# GPS_logger_Shield-v10.net
KiCad netlist of a schematic drawn in EAGLE
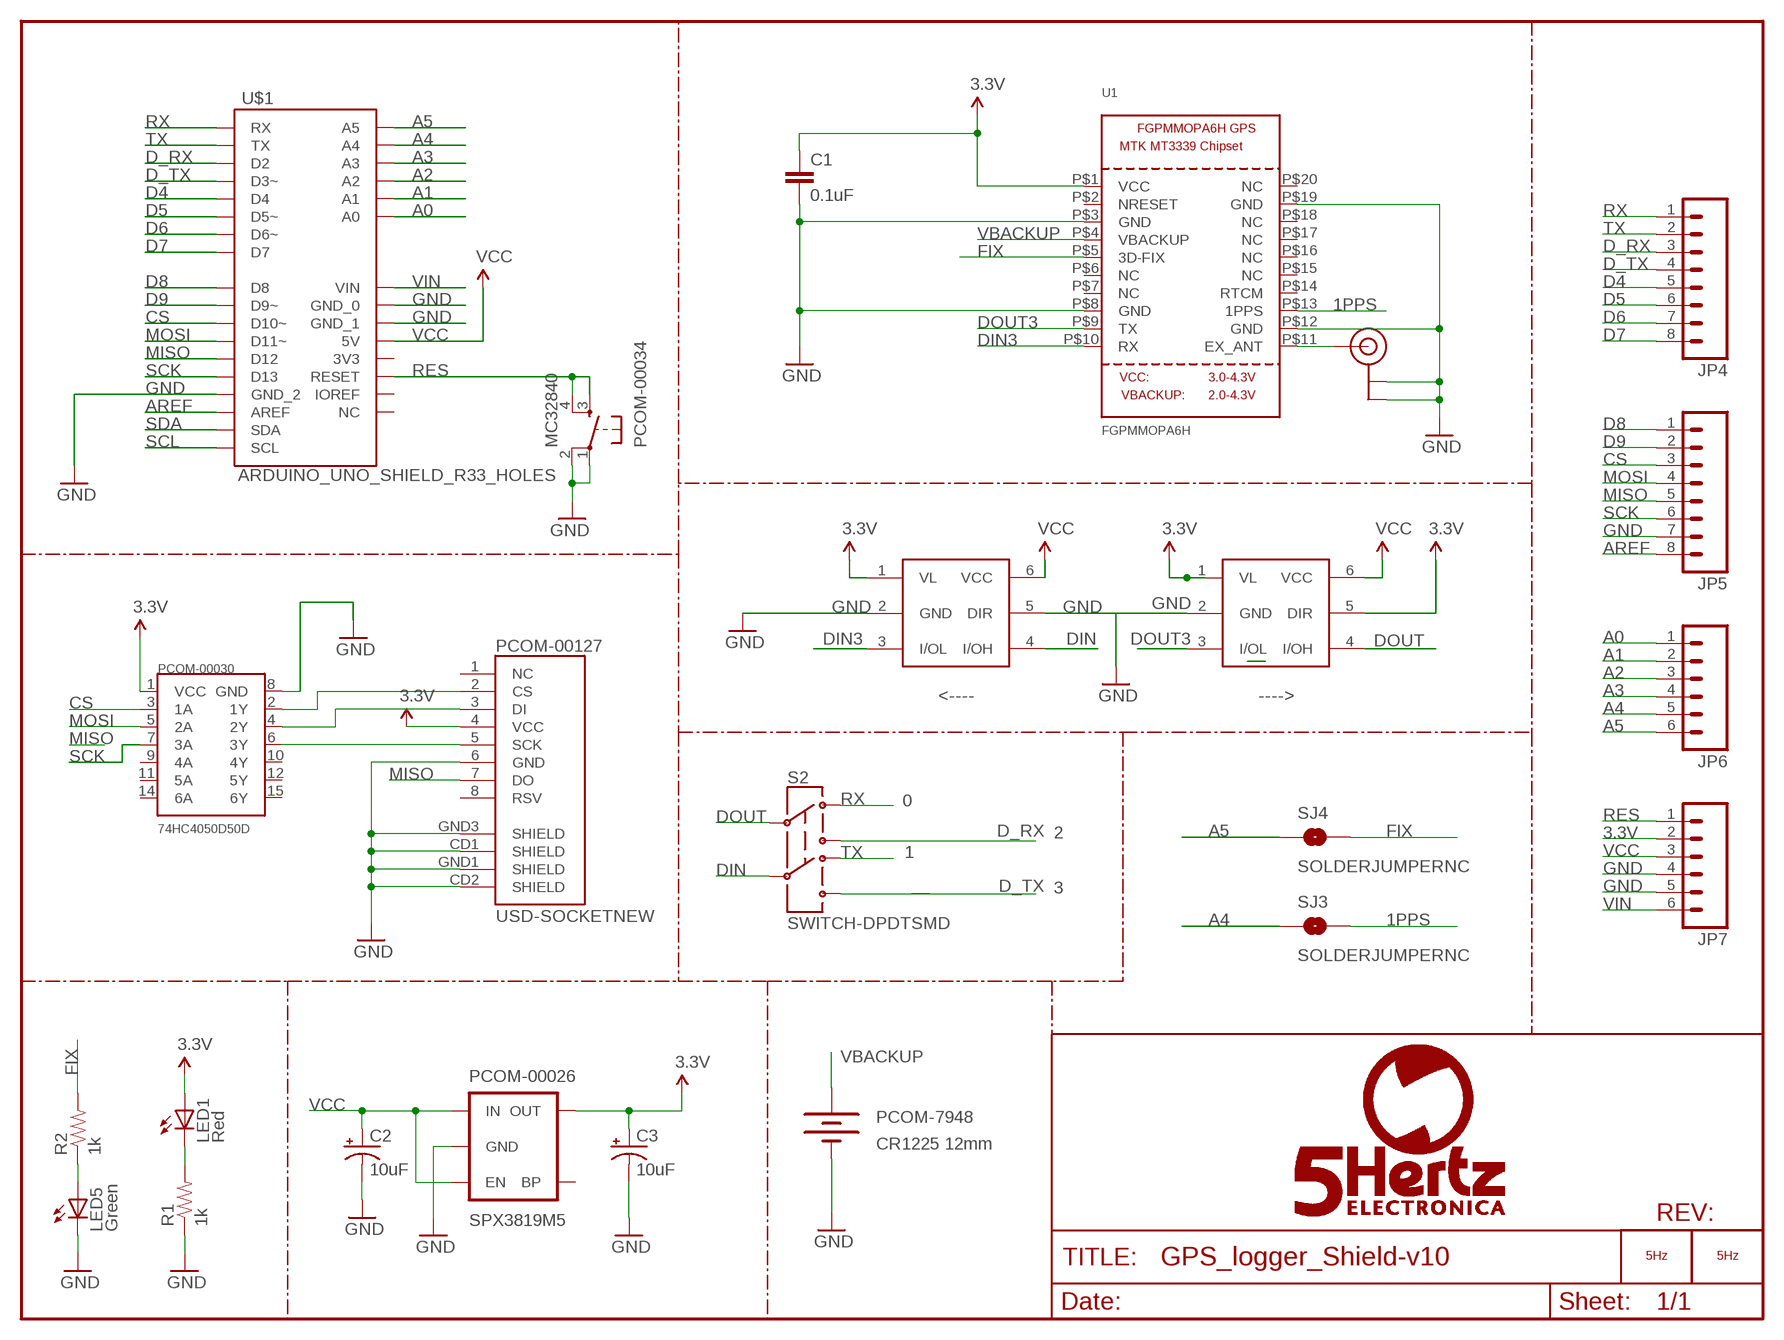
[diagram p0: schematic, sheet 1]

(export (version "E")
  (design (tool "Eeschema 10.0.6"))
  (components
    (comp (ref "C1")
      (value "0.1uF")
      (footprint "eagle-import:0603-CAP")
      (libsource (lib "eagle-import") (part "CAP0603-CAP"))
    )
    (comp (ref "C2")
      (value "10uF")
      (footprint "eagle-import:EIA3216")
      (libsource (lib "eagle-import") (part "CAP_POL1206"))
    )
    (comp (ref "C3")
      (value "10uF")
      (footprint "eagle-import:EIA3216")
      (libsource (lib "eagle-import") (part "CAP_POL1206"))
    )
    (comp (ref "JP4")
      (value "M08")
      (footprint "eagle-import:1X08")
      (libsource (lib "eagle-import") (part "M08"))
    )
    (comp (ref "JP5")
      (value "M08")
      (footprint "eagle-import:1X08")
      (libsource (lib "eagle-import") (part "M08"))
    )
    (comp (ref "JP6")
      (value "M06SIP")
      (footprint "eagle-import:1X06")
      (libsource (lib "eagle-import") (part "M06SIP"))
    )
    (comp (ref "JP7")
      (value "M06SIP")
      (footprint "eagle-import:1X06")
      (libsource (lib "eagle-import") (part "M06SIP"))
    )
    (comp (ref "LED1")
      (value "Red")
      (footprint "eagle-import:LED-0603")
      (libsource (lib "eagle-import") (part "LED0603"))
    )
    (comp (ref "LED5")
      (value "Green")
      (footprint "eagle-import:LED-0603")
      (libsource (lib "eagle-import") (part "LED0603"))
    )
    (comp (ref "LOGO1")
      (value "LOGO_5HZ_H_COOPER_15MM")
      (footprint "eagle-import:5HZ_LOGO_H_COOPER_15MM")
      (libsource (lib "eagle-import") (part "LOGO_5HZ_H_COOPER_15MM"))
    )
    (comp (ref "LOGO2")
      (value "LOGO_5HZ_MAIN_10MM")
      (footprint "eagle-import:5HZ_LOGO_MAIN_10MM")
      (libsource (lib "eagle-import") (part "LOGO_5HZ_MAIN_10MM"))
    )
    (comp (ref "PCOM-00026")
      (value "SPX3819M5")
      (footprint "eagle-import:SOT23-5")
      (libsource (lib "eagle-import") (part "V_REG_LDOSMD"))
    )
    (comp (ref "PCOM-00030")
      (value "74HC4050D50D")
      (footprint "eagle-import:SO016")
      (libsource (lib "eagle-import") (part "HEX_CONVERTER"))
    )
    (comp (ref "PCOM-00034")
      (value "MC32840")
      (footprint "eagle-import:TACTILE_SWITCH_SMD")
      (libsource (lib "eagle-import") (part "TAC_SWITCHSMD"))
    )
    (comp (ref "PCOM-00127")
      (value "USD-SOCKETNEW")
      (footprint "eagle-import:MICRO-SD-SOCKET-PP")
      (libsource (lib "eagle-import") (part "USD-SOCKETNEW"))
    )
    (comp (ref "PCOM-7948")
      (value "CR1225 12mm")
      (footprint "eagle-import:BATTCON_12MM_PTH")
      (libsource (lib "eagle-import") (part "BATTERY12PTH"))
    )
    (comp (ref "R1")
      (value "1k")
      (footprint "eagle-import:0603-RES")
      (libsource (lib "eagle-import") (part "RESISTOR0603-RES"))
    )
    (comp (ref "R2")
      (value "1k")
      (footprint "eagle-import:0603-RES")
      (libsource (lib "eagle-import") (part "RESISTOR0603-RES"))
    )
    (comp (ref "S2")
      (value "SWITCH-DPDTSMD")
      (footprint "eagle-import:AYZ0202")
      (libsource (lib "eagle-import") (part "SWITCH-DPDTSMD"))
    )
    (comp (ref "SJ3")
      (value "SOLDERJUMPERNC")
      (footprint "eagle-import:SJ_2S")
      (libsource (lib "eagle-import") (part "SOLDERJUMPERNC"))
    )
    (comp (ref "SJ4")
      (value "SOLDERJUMPERNC")
      (footprint "eagle-import:SJ_2S")
      (libsource (lib "eagle-import") (part "SOLDERJUMPERNC"))
    )
    (comp (ref "U$1")
      (value "ARDUINO_UNO_SHIELD_R33_HOLES")
      (footprint "eagle-import:UNO_R3_SHIELD_3_HOLES_NO_SILK")
      (libsource (lib "eagle-import") (part "ARDUINO_UNO_SHIELD_R33_HOLES"))
    )
    (comp (ref "U$7")
      (value "MAX337")
      (footprint "eagle-import:SOT-363")
      (libsource (lib "eagle-import") (part "MAX337"))
    )
    (comp (ref "U$8")
      (value "MAX337")
      (footprint "eagle-import:SOT-363")
      (libsource (lib "eagle-import") (part "MAX337"))
    )
    (comp (ref "U$20")
      (value "U.FL")
      (footprint "eagle-import:U.FL")
      (libsource (lib "eagle-import") (part "U.FL"))
    )
    (comp (ref "U1")
      (value "FGPMMOPA6H")
      (footprint "eagle-import:FGPMMOPA6H")
      (libsource (lib "eagle-import") (part "GPS_FGPMMOPA6H"))
    )
  )
  (nets
    (net (code "1") (name "/1PPS") (class "Default")
      (node (ref "SJ3") (pin "2") (pinfunction "2_2") (pintype "passive"))
      (node (ref "U1") (pin "P$13") (pinfunction "1PPS_P$13") (pintype "bidirectional"))
    )
    (net (code "2") (name "/A0") (class "Default")
      (node (ref "JP6") (pin "1") (pinfunction "1_1") (pintype "passive"))
      (node (ref "U$1") (pin "A0") (pinfunction "A0_A0") (pintype "bidirectional"))
    )
    (net (code "3") (name "/A1") (class "Default")
      (node (ref "JP6") (pin "2") (pinfunction "2_2") (pintype "passive"))
      (node (ref "U$1") (pin "A1") (pinfunction "A1_A1") (pintype "bidirectional"))
    )
    (net (code "4") (name "/A2") (class "Default")
      (node (ref "JP6") (pin "3") (pinfunction "3_3") (pintype "passive"))
      (node (ref "U$1") (pin "A2") (pinfunction "A2_A2") (pintype "bidirectional"))
    )
    (net (code "5") (name "/A3") (class "Default")
      (node (ref "JP6") (pin "4") (pinfunction "4_4") (pintype "passive"))
      (node (ref "U$1") (pin "A3") (pinfunction "A3_A3") (pintype "bidirectional"))
    )
    (net (code "6") (name "/A4") (class "Default")
      (node (ref "JP6") (pin "5") (pinfunction "5_5") (pintype "passive"))
      (node (ref "SJ3") (pin "1") (pinfunction "1_1") (pintype "passive"))
      (node (ref "U$1") (pin "A4") (pinfunction "A4_A4") (pintype "bidirectional"))
    )
    (net (code "7") (name "/A5") (class "Default")
      (node (ref "JP6") (pin "6") (pinfunction "6_6") (pintype "passive"))
      (node (ref "SJ4") (pin "1") (pinfunction "1_1") (pintype "passive"))
      (node (ref "U$1") (pin "A5") (pinfunction "A5_A5") (pintype "bidirectional"))
    )
    (net (code "8") (name "/AREF") (class "Default")
      (node (ref "JP5") (pin "8") (pinfunction "8_8") (pintype "passive"))
      (node (ref "U$1") (pin "AREF") (pinfunction "AREF_AREF") (pintype "bidirectional"))
    )
    (net (code "9") (name "/CS") (class "Default")
      (node (ref "JP5") (pin "3") (pinfunction "3_3") (pintype "passive"))
      (node (ref "PCOM-00030") (pin "3") (pinfunction "1A_3") (pintype "bidirectional"))
      (node (ref "U$1") (pin "D10") (pinfunction "D10~{}_D10") (pintype "bidirectional"))
    )
    (net (code "10") (name "/D4") (class "Default")
      (node (ref "JP4") (pin "5") (pinfunction "5_5") (pintype "passive"))
      (node (ref "U$1") (pin "D4") (pinfunction "D4_D4") (pintype "bidirectional"))
    )
    (net (code "11") (name "/D5") (class "Default")
      (node (ref "JP4") (pin "6") (pinfunction "6_6") (pintype "passive"))
      (node (ref "U$1") (pin "D5") (pinfunction "D5~{}_D5") (pintype "bidirectional"))
    )
    (net (code "12") (name "/D6") (class "Default")
      (node (ref "JP4") (pin "7") (pinfunction "7_7") (pintype "passive"))
      (node (ref "U$1") (pin "D6") (pinfunction "D6~{}_D6") (pintype "bidirectional"))
    )
    (net (code "13") (name "/D7") (class "Default")
      (node (ref "JP4") (pin "8") (pinfunction "8_8") (pintype "passive"))
      (node (ref "U$1") (pin "D7") (pinfunction "D7_D7") (pintype "bidirectional"))
    )
    (net (code "14") (name "/D8") (class "Default")
      (node (ref "JP5") (pin "1") (pinfunction "1_1") (pintype "passive"))
      (node (ref "U$1") (pin "D8") (pinfunction "D8_D8") (pintype "bidirectional"))
    )
    (net (code "15") (name "/D9") (class "Default")
      (node (ref "JP5") (pin "2") (pinfunction "2_2") (pintype "passive"))
      (node (ref "U$1") (pin "D9") (pinfunction "D9~{}_D9") (pintype "bidirectional"))
    )
    (net (code "16") (name "/DIN") (class "Default")
      (node (ref "S2") (pin "5") (pinfunction "5_5") (pintype "bidirectional"))
      (node (ref "U$7") (pin "4") (pinfunction "I/OH_4") (pintype "bidirectional"))
    )
    (net (code "17") (name "/DIN3") (class "Default")
      (node (ref "U$7") (pin "3") (pinfunction "I/OL_3") (pintype "bidirectional"))
      (node (ref "U1") (pin "P$10") (pinfunction "RX_P$10") (pintype "bidirectional"))
    )
    (net (code "18") (name "/DOUT") (class "Default")
      (node (ref "S2") (pin "2") (pinfunction "2_2") (pintype "bidirectional"))
      (node (ref "U$8") (pin "4") (pinfunction "I/OH_4") (pintype "bidirectional"))
    )
    (net (code "19") (name "/DOUT3") (class "Default")
      (node (ref "U$8") (pin "3") (pinfunction "I/OL_3") (pintype "bidirectional"))
      (node (ref "U1") (pin "P$9") (pinfunction "TX_P$9") (pintype "bidirectional"))
    )
    (net (code "20") (name "/D_RX") (class "Default")
      (node (ref "JP4") (pin "3") (pinfunction "3_3") (pintype "passive"))
      (node (ref "S2") (pin "3") (pinfunction "3_3") (pintype "bidirectional"))
      (node (ref "U$1") (pin "D2") (pinfunction "D2_D2") (pintype "bidirectional"))
    )
    (net (code "21") (name "/D_TX") (class "Default")
      (node (ref "JP4") (pin "4") (pinfunction "4_4") (pintype "passive"))
      (node (ref "S2") (pin "6") (pinfunction "6_6") (pintype "bidirectional"))
      (node (ref "U$1") (pin "D3") (pinfunction "D3~{}_D3") (pintype "bidirectional"))
    )
    (net (code "22") (name "/FIX") (class "Default")
      (node (ref "R2") (pin "2") (pinfunction "2_2") (pintype "passive"))
      (node (ref "SJ4") (pin "2") (pinfunction "2_2") (pintype "passive"))
      (node (ref "U1") (pin "P$5") (pinfunction "3D-FIX_P$5") (pintype "bidirectional"))
    )
    (net (code "23") (name "/MISO") (class "Default")
      (node (ref "JP5") (pin "5") (pinfunction "5_5") (pintype "passive"))
      (node (ref "PCOM-00127") (pin "7") (pinfunction "DO_7") (pintype "bidirectional"))
      (node (ref "U$1") (pin "D12") (pinfunction "D12_D12") (pintype "bidirectional"))
    )
    (net (code "24") (name "/MOSI") (class "Default")
      (node (ref "JP5") (pin "4") (pinfunction "4_4") (pintype "passive"))
      (node (ref "PCOM-00030") (pin "5") (pinfunction "2A_5") (pintype "bidirectional"))
      (node (ref "U$1") (pin "D11") (pinfunction "D11~{}_D11") (pintype "bidirectional"))
    )
    (net (code "25") (name "/RES") (class "Default")
      (node (ref "JP7") (pin "1") (pinfunction "1_1") (pintype "passive"))
      (node (ref "PCOM-00034") (pin "3") (pinfunction "3_3") (pintype "passive"))
      (node (ref "PCOM-00034") (pin "4") (pinfunction "4_4") (pintype "passive"))
      (node (ref "U$1") (pin "RES") (pinfunction "RESET_RES") (pintype "bidirectional"))
    )
    (net (code "26") (name "/RX") (class "Default")
      (node (ref "JP4") (pin "1") (pinfunction "1_1") (pintype "passive"))
      (node (ref "S2") (pin "1") (pinfunction "1_1") (pintype "bidirectional"))
      (node (ref "U$1") (pin "RX") (pinfunction "RX_RX") (pintype "bidirectional"))
    )
    (net (code "27") (name "/SCK") (class "Default")
      (node (ref "JP5") (pin "6") (pinfunction "6_6") (pintype "passive"))
      (node (ref "PCOM-00030") (pin "7") (pinfunction "3A_7") (pintype "bidirectional"))
      (node (ref "U$1") (pin "D13") (pinfunction "D13_D13") (pintype "bidirectional"))
    )
    (net (code "28") (name "/SCL") (class "Default")
      (node (ref "U$1") (pin "SCL") (pinfunction "SCL_SCL") (pintype "bidirectional"))
    )
    (net (code "29") (name "/SDA") (class "Default")
      (node (ref "U$1") (pin "SDA") (pinfunction "SDA_SDA") (pintype "bidirectional"))
    )
    (net (code "30") (name "/TX") (class "Default")
      (node (ref "JP4") (pin "2") (pinfunction "2_2") (pintype "passive"))
      (node (ref "S2") (pin "4") (pinfunction "4_4") (pintype "bidirectional"))
      (node (ref "U$1") (pin "TX") (pinfunction "TX_TX") (pintype "bidirectional"))
    )
    (net (code "31") (name "/VBACKUP") (class "Default")
      (node (ref "PCOM-7948") (pin "VCC@1") (pinfunction "+_VCC@1") (pintype "power_in"))
      (node (ref "U1") (pin "P$4") (pinfunction "VBACKUP_P$4") (pintype "bidirectional"))
    )
    (net (code "32") (name "/VIN") (class "Default")
      (node (ref "JP7") (pin "6") (pinfunction "6_6") (pintype "passive"))
      (node (ref "U$1") (pin "VIN") (pinfunction "VIN_VIN") (pintype "bidirectional"))
    )
    (net (code "33") (name "3.3V") (class "Default")
      (node (ref "C1") (pin "1") (pinfunction "1_1") (pintype "passive"))
      (node (ref "C3") (pin "A") (pinfunction "+_A") (pintype "passive"))
      (node (ref "JP7") (pin "2") (pinfunction "2_2") (pintype "passive"))
      (node (ref "LED1") (pin "A") (pinfunction "A_A") (pintype "passive"))
      (node (ref "PCOM-00026") (pin "5") (pinfunction "OUT_5") (pintype "passive"))
      (node (ref "PCOM-00030") (pin "1") (pinfunction "VCC_1") (pintype "bidirectional"))
      (node (ref "PCOM-00127") (pin "4") (pinfunction "VCC_4") (pintype "bidirectional"))
      (node (ref "U$7") (pin "1") (pinfunction "VL_1") (pintype "bidirectional"))
      (node (ref "U$8") (pin "1") (pinfunction "VL_1") (pintype "bidirectional"))
      (node (ref "U$8") (pin "5") (pinfunction "DIR_5") (pintype "bidirectional"))
      (node (ref "U1") (pin "P$1") (pinfunction "VCC_P$1") (pintype "bidirectional"))
    )
    (net (code "34") (name "GND") (class "Default")
      (node (ref "C1") (pin "2") (pinfunction "2_2") (pintype "passive"))
      (node (ref "C2") (pin "C") (pinfunction "-_C") (pintype "passive"))
      (node (ref "C3") (pin "C") (pinfunction "-_C") (pintype "passive"))
      (node (ref "JP5") (pin "7") (pinfunction "7_7") (pintype "passive"))
      (node (ref "JP7") (pin "4") (pinfunction "4_4") (pintype "passive"))
      (node (ref "JP7") (pin "5") (pinfunction "5_5") (pintype "passive"))
      (node (ref "LED5") (pin "C") (pinfunction "C_C") (pintype "passive"))
      (node (ref "PCOM-00026") (pin "2") (pinfunction "GND_2") (pintype "input"))
      (node (ref "PCOM-00030") (pin "8") (pinfunction "GND_8") (pintype "bidirectional"))
      (node (ref "PCOM-00034") (pin "1") (pinfunction "1_1") (pintype "passive"))
      (node (ref "PCOM-00034") (pin "2") (pinfunction "2_2") (pintype "passive"))
      (node (ref "PCOM-00127") (pin "6") (pinfunction "GND_6") (pintype "bidirectional"))
      (node (ref "PCOM-00127") (pin "CD1") (pinfunction "SHIELD_CD1") (pintype "bidirectional"))
      (node (ref "PCOM-00127") (pin "CD2") (pinfunction "SHIELD_CD2") (pintype "bidirectional"))
      (node (ref "PCOM-00127") (pin "GND1") (pinfunction "SHIELD_GND1") (pintype "bidirectional"))
      (node (ref "PCOM-00127") (pin "GND3") (pinfunction "SHIELD_GND3") (pintype "bidirectional"))
      (node (ref "PCOM-7948") (pin "GND") (pinfunction "-_GND") (pintype "power_in"))
      (node (ref "R1") (pin "1") (pinfunction "1_1") (pintype "passive"))
      (node (ref "U$1") (pin "GND_0") (pinfunction "GND_0_GND_0") (pintype "bidirectional"))
      (node (ref "U$1") (pin "GND_1") (pinfunction "GND_1_GND_1") (pintype "bidirectional"))
      (node (ref "U$1") (pin "GND_2") (pinfunction "GND_2_GND_2") (pintype "bidirectional"))
      (node (ref "U$20") (pin "P$1") (pinfunction "GND_P$1") (pintype "bidirectional"))
      (node (ref "U$20") (pin "P$2") (pinfunction "GND_P$2") (pintype "bidirectional"))
      (node (ref "U$7") (pin "2") (pinfunction "GND_2") (pintype "bidirectional"))
      (node (ref "U$7") (pin "5") (pinfunction "DIR_5") (pintype "bidirectional"))
      (node (ref "U$8") (pin "2") (pinfunction "GND_2") (pintype "bidirectional"))
      (node (ref "U1") (pin "P$12") (pinfunction "GND_P$12") (pintype "bidirectional"))
      (node (ref "U1") (pin "P$19") (pinfunction "GND_P$19") (pintype "bidirectional"))
      (node (ref "U1") (pin "P$3") (pinfunction "GND_P$3") (pintype "bidirectional"))
      (node (ref "U1") (pin "P$8") (pinfunction "GND_P$8") (pintype "bidirectional"))
    )
    (net (code "35") (name "Net-(LED1-PadC)") (class "Default")
      (node (ref "LED1") (pin "C") (pinfunction "C_C") (pintype "passive"))
      (node (ref "R1") (pin "2") (pinfunction "2_2") (pintype "passive"))
    )
    (net (code "36") (name "Net-(LED5-PadA)") (class "Default")
      (node (ref "LED5") (pin "A") (pinfunction "A_A") (pintype "passive"))
      (node (ref "R2") (pin "1") (pinfunction "1_1") (pintype "passive"))
    )
    (net (code "37") (name "Net-(PCOM-00030-1Y)") (class "Default")
      (node (ref "PCOM-00030") (pin "2") (pinfunction "1Y_2") (pintype "bidirectional"))
      (node (ref "PCOM-00127") (pin "2") (pinfunction "CS_2") (pintype "bidirectional"))
    )
    (net (code "38") (name "Net-(PCOM-00030-2Y)") (class "Default")
      (node (ref "PCOM-00030") (pin "4") (pinfunction "2Y_4") (pintype "bidirectional"))
      (node (ref "PCOM-00127") (pin "3") (pinfunction "DI_3") (pintype "bidirectional"))
    )
    (net (code "39") (name "Net-(PCOM-00030-3Y)") (class "Default")
      (node (ref "PCOM-00030") (pin "6") (pinfunction "3Y_6") (pintype "bidirectional"))
      (node (ref "PCOM-00127") (pin "5") (pinfunction "SCK_5") (pintype "bidirectional"))
    )
    (net (code "40") (name "Net-(U$20-SIGNAL)") (class "Default")
      (node (ref "U$20") (pin "P$3") (pinfunction "SIGNAL_P$3") (pintype "bidirectional"))
      (node (ref "U1") (pin "P$11") (pinfunction "EX_ANT_P$11") (pintype "bidirectional"))
    )
    (net (code "41") (name "VCC") (class "Default")
      (node (ref "C2") (pin "A") (pinfunction "+_A") (pintype "passive"))
      (node (ref "JP7") (pin "3") (pinfunction "3_3") (pintype "passive"))
      (node (ref "PCOM-00026") (pin "1") (pinfunction "IN_1") (pintype "input"))
      (node (ref "PCOM-00026") (pin "3") (pinfunction "EN_3") (pintype "input"))
      (node (ref "U$1") (pin "5V") (pinfunction "5V_5V") (pintype "bidirectional"))
      (node (ref "U$7") (pin "6") (pinfunction "VCC_6") (pintype "bidirectional"))
      (node (ref "U$8") (pin "6") (pinfunction "VCC_6") (pintype "bidirectional"))
    )
    (net (code "42") (name "unconnected-(PCOM-00026-BP-Pad4)") (class "Default")
      (node (ref "PCOM-00026") (pin "4") (pinfunction "BP_4") (pintype "input"))
    )
    (net (code "43") (name "unconnected-(PCOM-00030-4A-Pad9)") (class "Default")
      (node (ref "PCOM-00030") (pin "9") (pinfunction "4A_9") (pintype "bidirectional"))
    )
    (net (code "44") (name "unconnected-(PCOM-00030-4Y-Pad10)") (class "Default")
      (node (ref "PCOM-00030") (pin "10") (pinfunction "4Y_10") (pintype "bidirectional"))
    )
    (net (code "45") (name "unconnected-(PCOM-00030-5A-Pad11)") (class "Default")
      (node (ref "PCOM-00030") (pin "11") (pinfunction "5A_11") (pintype "bidirectional"))
    )
    (net (code "46") (name "unconnected-(PCOM-00030-5Y-Pad12)") (class "Default")
      (node (ref "PCOM-00030") (pin "12") (pinfunction "5Y_12") (pintype "bidirectional"))
    )
    (net (code "47") (name "unconnected-(PCOM-00030-6A-Pad14)") (class "Default")
      (node (ref "PCOM-00030") (pin "14") (pinfunction "6A_14") (pintype "bidirectional"))
    )
    (net (code "48") (name "unconnected-(PCOM-00030-6Y-Pad15)") (class "Default")
      (node (ref "PCOM-00030") (pin "15") (pinfunction "6Y_15") (pintype "bidirectional"))
    )
    (net (code "49") (name "unconnected-(PCOM-00127-NC-Pad1)") (class "Default")
      (node (ref "PCOM-00127") (pin "1") (pinfunction "NC_1") (pintype "bidirectional"))
    )
    (net (code "50") (name "unconnected-(PCOM-00127-RSV-Pad8)") (class "Default")
      (node (ref "PCOM-00127") (pin "8") (pinfunction "RSV_8") (pintype "bidirectional"))
    )
    (net (code "51") (name "unconnected-(U$1-3V3-Pad3.3V)") (class "Default")
      (node (ref "U$1") (pin "3.3V") (pinfunction "3V3_3.3V") (pintype "bidirectional"))
    )
    (net (code "52") (name "unconnected-(U$1-PadIOREF)") (class "Default")
      (node (ref "U$1") (pin "IOREF") (pinfunction "IOREF_IOREF") (pintype "bidirectional"))
    )
    (net (code "53") (name "unconnected-(U$1-PadNC)") (class "Default")
      (node (ref "U$1") (pin "NC") (pinfunction "NC_NC") (pintype "no_connect"))
    )
    (net (code "54") (name "unconnected-(U1-NC-PadP$6)") (class "Default")
      (node (ref "U1") (pin "P$6") (pinfunction "NC_P$6") (pintype "bidirectional"))
    )
    (net (code "55") (name "unconnected-(U1-NC-PadP$7)") (class "Default")
      (node (ref "U1") (pin "P$7") (pinfunction "NC_P$7") (pintype "bidirectional"))
    )
    (net (code "56") (name "unconnected-(U1-NC-PadP$15)") (class "Default")
      (node (ref "U1") (pin "P$15") (pinfunction "NC_P$15") (pintype "bidirectional"))
    )
    (net (code "57") (name "unconnected-(U1-NC-PadP$16)") (class "Default")
      (node (ref "U1") (pin "P$16") (pinfunction "NC_P$16") (pintype "bidirectional"))
    )
    (net (code "58") (name "unconnected-(U1-NC-PadP$17)") (class "Default")
      (node (ref "U1") (pin "P$17") (pinfunction "NC_P$17") (pintype "bidirectional"))
    )
    (net (code "59") (name "unconnected-(U1-NC-PadP$18)") (class "Default")
      (node (ref "U1") (pin "P$18") (pinfunction "NC_P$18") (pintype "bidirectional"))
    )
    (net (code "60") (name "unconnected-(U1-NC-PadP$20)") (class "Default")
      (node (ref "U1") (pin "P$20") (pinfunction "NC_P$20") (pintype "bidirectional"))
    )
    (net (code "61") (name "unconnected-(U1-NRESET-PadP$2)") (class "Default")
      (node (ref "U1") (pin "P$2") (pinfunction "NRESET_P$2") (pintype "bidirectional"))
    )
    (net (code "62") (name "unconnected-(U1-RTCM-PadP$14)") (class "Default")
      (node (ref "U1") (pin "P$14") (pinfunction "RTCM_P$14") (pintype "bidirectional"))
    )
  )
)
